# schemetic_phongbep.net
KiCad netlist of a schematic drawn in Altium Designer
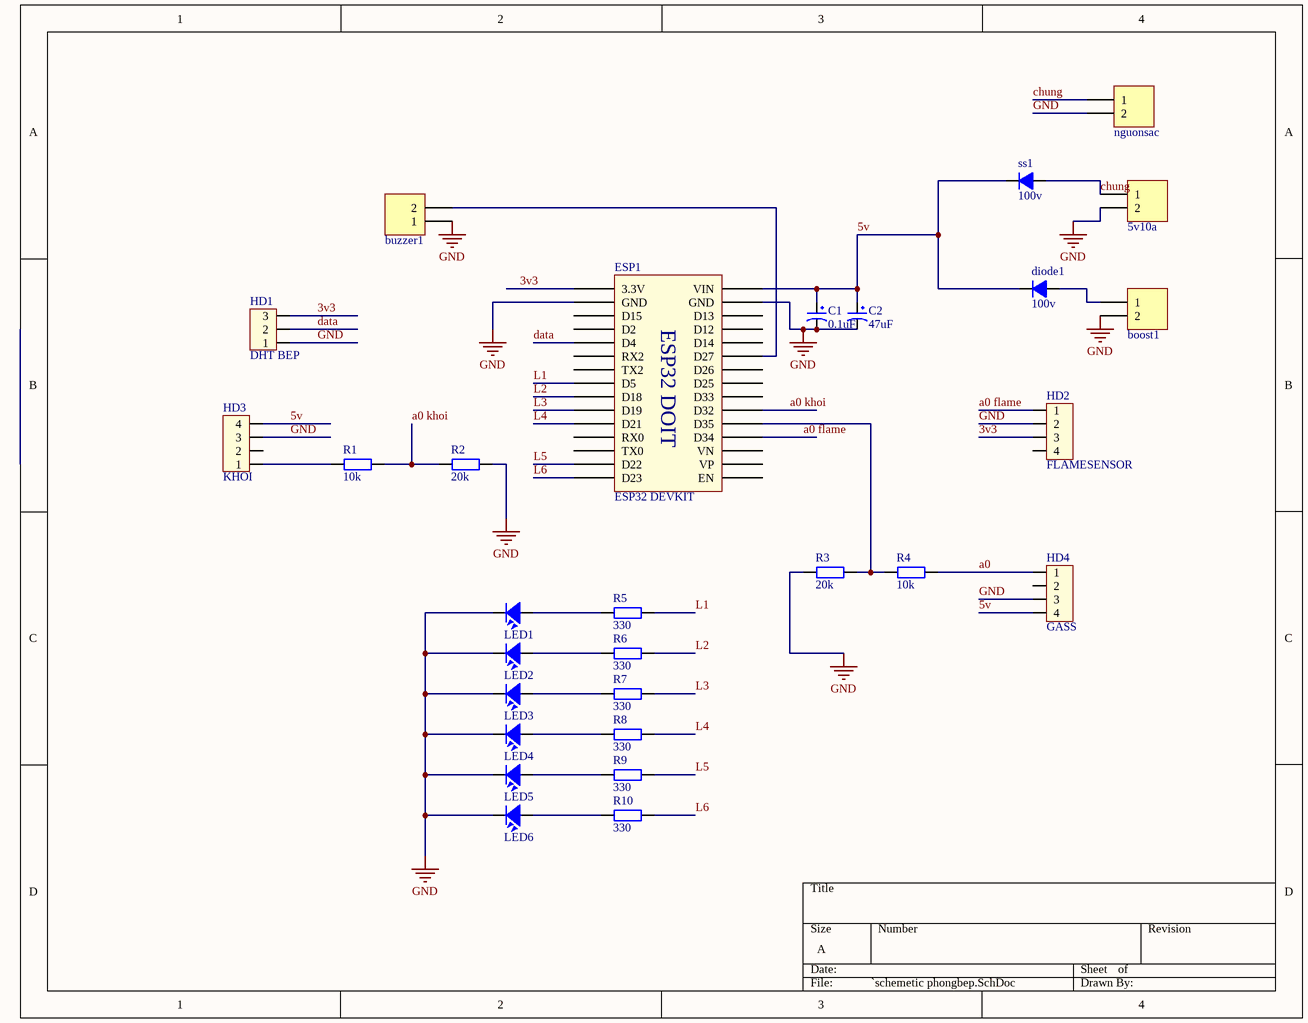
[diagram p0: `schemetic phongbep.SchDoc]

(export (version "E")
  (design (tool "Eeschema 10.0.6"))
  (components
    (comp (ref "5v10a")
      (value "Header 2_1")
      (footprint "HED2")
      (description "Header, 2-Pin")
      (fields (field (name "MANUFACTURER") "Generic Components"))
      (libsource (lib "") (part "Header 2_1_1"))
    )
    (comp (ref "boost1")
      (value "Header 2_1")
      (footprint "HED2")
      (description "Header, 2-Pin")
      (fields (field (name "MANUFACTURER") "Generic Components"))
      (libsource (lib "") (part "Header 2_1_1"))
    )
    (comp (ref "buzzer1")
      (value "Header 2_1")
      (footprint "HED2")
      (description "Header, 2-Pin")
      (fields (field (name "MANUFACTURER") "Generic Components"))
      (libsource (lib "syhaunguyen") (part "Header 2_1"))
    )
    (comp (ref "C1")
      (value "0.1uF")
      (footprint "tu hoa 5mm")
      (description "Cắm")
      (libsource (lib "Altium_Lib_by_KhueNguyenCreator") (part "Tu Hoa 0.1uF 50V 5x11"))
    )
    (comp (ref "C2")
      (value "47uF")
      (footprint "tu hoa 5mm")
      (description "Cắm")
      (libsource (lib "Altium_Lib_by_KhueNguyenCreator") (part "Tu Hoa 47uF 16V 5x10"))
    )
    (comp (ref "diode1")
      (value "100v")
      (footprint "DIODE 0.5A")
      (description "Cắm")
      (libsource (lib "Altium_Lib_by_KhueNguyenCreator") (part "Diode 1N4148"))
    )
    (comp (ref "ESP1")
      (value "ESP32 DEVKIT")
      (footprint "ESP32 WROOM 32 KIT")
      (libsource (lib "Altium_Lib_by_KhueNguyenCreator") (part "ESP32 WROOM 32 KIT"))
    )
    (comp (ref "HD1")
      (value "DHT BEP")
      (footprint "HED3")
      (description "Header 3 (Green)")
      (libsource (lib "syhaunguyen") (part "Hed3"))
    )
    (comp (ref "HD2")
      (value "FLAMESENSOR")
      (footprint "HED4")
      (description "Header 4 (Green)")
      (libsource (lib "syhaunguyen") (part "Hed4"))
    )
    (comp (ref "HD3")
      (value "KHOI")
      (footprint "HED4")
      (description "Header 4 (Green)")
      (libsource (lib "") (part "Hed4_1"))
    )
    (comp (ref "HD4")
      (value "GASS")
      (footprint "HED4")
      (description "Header 4 (Green)")
      (libsource (lib "syhaunguyen") (part "Hed4"))
    )
    (comp (ref "LED1")
      (value "LED")
      (footprint "LED-5-Green")
      (description "LED Single colour Green and Red")
      (libsource (lib "syhaunguyen") (part "LED"))
    )
    (comp (ref "LED2")
      (value "LED")
      (footprint "LED-5-Green")
      (description "LED Single colour Green and Red")
      (libsource (lib "syhaunguyen") (part "LED"))
    )
    (comp (ref "LED3")
      (value "LED")
      (footprint "LED-5-Green")
      (description "LED Single colour Green and Red")
      (libsource (lib "syhaunguyen") (part "LED"))
    )
    (comp (ref "LED4")
      (value "LED")
      (footprint "LED-5-Green")
      (description "LED Single colour Green and Red")
      (libsource (lib "syhaunguyen") (part "LED"))
    )
    (comp (ref "LED5")
      (value "LED")
      (footprint "LED-5-Green")
      (description "LED Single colour Green and Red")
      (libsource (lib "syhaunguyen") (part "LED"))
    )
    (comp (ref "LED6")
      (value "LED")
      (footprint "LED-5-Green")
      (description "LED Single colour Green and Red")
      (libsource (lib "syhaunguyen") (part "LED"))
    )
    (comp (ref "nguonsac")
      (value "Header 2_1")
      (footprint "HED2")
      (description "Header, 2-Pin")
      (fields (field (name "MANUFACTURER") "Generic Components"))
      (libsource (lib "") (part "Header 2_1_1"))
    )
    (comp (ref "R1")
      (value "10k")
      (footprint "R1/4W")
      (description "Resistor 1/4W")
      (libsource (lib "syhaunguyen") (part "R1/4W"))
    )
    (comp (ref "R2")
      (value "20k")
      (footprint "R1/4W")
      (description "Resistor 1/4W")
      (libsource (lib "syhaunguyen") (part "R1/4W"))
    )
    (comp (ref "R3")
      (value "20k")
      (footprint "R1/4W")
      (description "Resistor 1/4W")
      (libsource (lib "syhaunguyen") (part "R1/4W"))
    )
    (comp (ref "R4")
      (value "10k")
      (footprint "R1/4W")
      (description "Resistor 1/4W")
      (libsource (lib "syhaunguyen") (part "R1/4W"))
    )
    (comp (ref "R5")
      (value "330")
      (footprint "R1/4W")
      (description "Resistor 1/4W")
      (libsource (lib "syhaunguyen") (part "R1/4W"))
    )
    (comp (ref "R6")
      (value "330")
      (footprint "R1/4W")
      (description "Resistor 1/4W")
      (libsource (lib "syhaunguyen") (part "R1/4W"))
    )
    (comp (ref "R7")
      (value "330")
      (footprint "R1/4W")
      (description "Resistor 1/4W")
      (libsource (lib "syhaunguyen") (part "R1/4W"))
    )
    (comp (ref "R8")
      (value "330")
      (footprint "R1/4W")
      (description "Resistor 1/4W")
      (libsource (lib "syhaunguyen") (part "R1/4W"))
    )
    (comp (ref "R9")
      (value "330")
      (footprint "R1/4W")
      (description "Resistor 1/4W")
      (libsource (lib "syhaunguyen") (part "R1/4W"))
    )
    (comp (ref "R10")
      (value "330")
      (footprint "R1/4W")
      (description "Resistor 1/4W")
      (libsource (lib "syhaunguyen") (part "R1/4W"))
    )
    (comp (ref "ss1")
      (value "100v")
      (footprint "DIODE 0.5A")
      (description "Cắm")
      (libsource (lib "Altium_Lib_by_KhueNguyenCreator") (part "Diode 1N4148"))
    )
  )
  (nets
    (net (code "1") (name "/3v3") (class "Default")
      (node (ref "ESP1") (pin "16") (pinfunction "3.3V_16") (pintype "passive"))
      (node (ref "HD1") (pin "3") (pinfunction "3_3") (pintype "passive"))
      (node (ref "HD2") (pin "3") (pinfunction "3_3") (pintype "passive"))
    )
    (net (code "2") (name "/5v") (class "Default")
      (node (ref "C1") (pin "1") (pinfunction "1_1") (pintype "passive"))
      (node (ref "C2") (pin "1") (pinfunction "1_1") (pintype "passive"))
      (node (ref "ESP1") (pin "15") (pinfunction "VIN_15") (pintype "passive"))
      (node (ref "HD3") (pin "4") (pinfunction "4_4") (pintype "passive"))
      (node (ref "HD4") (pin "4") (pinfunction "4_4") (pintype "passive"))
      (node (ref "diode1") (pin "2") (pinfunction "K_2") (pintype "passive"))
      (node (ref "ss1") (pin "2") (pinfunction "K_2") (pintype "passive"))
    )
    (net (code "3") (name "/L1") (class "Default")
      (node (ref "ESP1") (pin "23") (pinfunction "D5_23") (pintype "passive"))
      (node (ref "R5") (pin "2") (pinfunction "2_2") (pintype "passive"))
    )
    (net (code "4") (name "/L2") (class "Default")
      (node (ref "ESP1") (pin "24") (pinfunction "D18_24") (pintype "passive"))
      (node (ref "R6") (pin "2") (pinfunction "2_2") (pintype "passive"))
    )
    (net (code "5") (name "/L3") (class "Default")
      (node (ref "ESP1") (pin "25") (pinfunction "D19_25") (pintype "passive"))
      (node (ref "R7") (pin "2") (pinfunction "2_2") (pintype "passive"))
    )
    (net (code "6") (name "/L4") (class "Default")
      (node (ref "ESP1") (pin "26") (pinfunction "D21_26") (pintype "passive"))
      (node (ref "R8") (pin "2") (pinfunction "2_2") (pintype "passive"))
    )
    (net (code "7") (name "/L5") (class "Default")
      (node (ref "ESP1") (pin "29") (pinfunction "D22_29") (pintype "passive"))
      (node (ref "R9") (pin "2") (pinfunction "2_2") (pintype "passive"))
    )
    (net (code "8") (name "/L6") (class "Default")
      (node (ref "ESP1") (pin "30") (pinfunction "D23_30") (pintype "passive"))
      (node (ref "R10") (pin "2") (pinfunction "2_2") (pintype "passive"))
    )
    (net (code "9") (name "/a0") (class "Default")
      (node (ref "HD4") (pin "1") (pinfunction "1_1") (pintype "passive"))
      (node (ref "R4") (pin "2") (pinfunction "2_2") (pintype "passive"))
    )
    (net (code "10") (name "/a0 flame") (class "Default")
      (node (ref "ESP1") (pin "4") (pinfunction "D34_4") (pintype "passive"))
      (node (ref "HD2") (pin "1") (pinfunction "1_1") (pintype "passive"))
    )
    (net (code "11") (name "/a0 khoi") (class "Default")
      (node (ref "ESP1") (pin "6") (pinfunction "D32_6") (pintype "passive"))
      (node (ref "R1") (pin "2") (pinfunction "2_2") (pintype "passive"))
      (node (ref "R2") (pin "2") (pinfunction "2_2") (pintype "passive"))
    )
    (net (code "12") (name "/chung") (class "Default")
      (node (ref "5v10a") (pin "1") (pinfunction "1_1") (pintype "passive"))
      (node (ref "nguonsac") (pin "1") (pinfunction "1_1") (pintype "passive"))
      (node (ref "ss1") (pin "1") (pinfunction "A_1") (pintype "passive"))
    )
    (net (code "13") (name "/data") (class "Default")
      (node (ref "ESP1") (pin "20") (pinfunction "D4_20") (pintype "passive"))
      (node (ref "HD1") (pin "2") (pinfunction "2_2") (pintype "passive"))
    )
    (net (code "14") (name "GND") (class "Default")
      (node (ref "5v10a") (pin "2") (pinfunction "2_2") (pintype "passive"))
      (node (ref "C1") (pin "2") (pinfunction "2_2") (pintype "passive"))
      (node (ref "C2") (pin "2") (pinfunction "2_2") (pintype "passive"))
      (node (ref "ESP1") (pin "14") (pinfunction "GND_14") (pintype "passive"))
      (node (ref "ESP1") (pin "17") (pinfunction "GND_17") (pintype "passive"))
      (node (ref "HD1") (pin "1") (pinfunction "1_1") (pintype "passive"))
      (node (ref "HD2") (pin "2") (pinfunction "2_2") (pintype "passive"))
      (node (ref "HD3") (pin "3") (pinfunction "3_3") (pintype "passive"))
      (node (ref "HD4") (pin "3") (pinfunction "3_3") (pintype "passive"))
      (node (ref "LED1") (pin "2") (pinfunction "2_2") (pintype "passive"))
      (node (ref "LED2") (pin "2") (pinfunction "2_2") (pintype "passive"))
      (node (ref "LED3") (pin "2") (pinfunction "2_2") (pintype "passive"))
      (node (ref "LED4") (pin "2") (pinfunction "2_2") (pintype "passive"))
      (node (ref "LED5") (pin "2") (pinfunction "2_2") (pintype "passive"))
      (node (ref "LED6") (pin "2") (pinfunction "2_2") (pintype "passive"))
      (node (ref "R2") (pin "1") (pinfunction "1_1") (pintype "passive"))
      (node (ref "R3") (pin "2") (pinfunction "2_2") (pintype "passive"))
      (node (ref "boost1") (pin "2") (pinfunction "2_2") (pintype "passive"))
      (node (ref "buzzer1") (pin "1") (pinfunction "1_1") (pintype "passive"))
      (node (ref "nguonsac") (pin "2") (pinfunction "2_2") (pintype "passive"))
    )
    (net (code "15") (name "Net-(ESP1-D27)") (class "Default")
      (node (ref "ESP1") (pin "10") (pinfunction "D27_10") (pintype "passive"))
      (node (ref "buzzer1") (pin "2") (pinfunction "2_2") (pintype "passive"))
    )
    (net (code "16") (name "Net-(ESP1-D35)") (class "Default")
      (node (ref "ESP1") (pin "5") (pinfunction "D35_5") (pintype "passive"))
      (node (ref "R3") (pin "1") (pinfunction "1_1") (pintype "passive"))
      (node (ref "R4") (pin "1") (pinfunction "1_1") (pintype "passive"))
    )
    (net (code "17") (name "Net-(HD3-Pad1)") (class "Default")
      (node (ref "HD3") (pin "1") (pinfunction "1_1") (pintype "passive"))
      (node (ref "R1") (pin "1") (pinfunction "1_1") (pintype "passive"))
    )
    (net (code "18") (name "Net-(LED1-Pad1)") (class "Default")
      (node (ref "LED1") (pin "1") (pinfunction "1_1") (pintype "passive"))
      (node (ref "R5") (pin "1") (pinfunction "1_1") (pintype "passive"))
    )
    (net (code "19") (name "Net-(LED2-Pad1)") (class "Default")
      (node (ref "LED2") (pin "1") (pinfunction "1_1") (pintype "passive"))
      (node (ref "R6") (pin "1") (pinfunction "1_1") (pintype "passive"))
    )
    (net (code "20") (name "Net-(LED3-Pad1)") (class "Default")
      (node (ref "LED3") (pin "1") (pinfunction "1_1") (pintype "passive"))
      (node (ref "R7") (pin "1") (pinfunction "1_1") (pintype "passive"))
    )
    (net (code "21") (name "Net-(LED4-Pad1)") (class "Default")
      (node (ref "LED4") (pin "1") (pinfunction "1_1") (pintype "passive"))
      (node (ref "R8") (pin "1") (pinfunction "1_1") (pintype "passive"))
    )
    (net (code "22") (name "Net-(LED5-Pad1)") (class "Default")
      (node (ref "LED5") (pin "1") (pinfunction "1_1") (pintype "passive"))
      (node (ref "R9") (pin "1") (pinfunction "1_1") (pintype "passive"))
    )
    (net (code "23") (name "Net-(LED6-Pad1)") (class "Default")
      (node (ref "LED6") (pin "1") (pinfunction "1_1") (pintype "passive"))
      (node (ref "R10") (pin "1") (pinfunction "1_1") (pintype "passive"))
    )
    (net (code "24") (name "Net-(diode1-A)") (class "Default")
      (node (ref "boost1") (pin "1") (pinfunction "1_1") (pintype "passive"))
      (node (ref "diode1") (pin "1") (pinfunction "A_1") (pintype "passive"))
    )
    (net (code "25") (name "unconnected-(ESP1-D2-Pad19)") (class "Default")
      (node (ref "ESP1") (pin "19") (pinfunction "D2_19") (pintype "passive"))
    )
    (net (code "26") (name "unconnected-(ESP1-D12-Pad12)") (class "Default")
      (node (ref "ESP1") (pin "12") (pinfunction "D12_12") (pintype "passive"))
    )
    (net (code "27") (name "unconnected-(ESP1-D13-Pad13)") (class "Default")
      (node (ref "ESP1") (pin "13") (pinfunction "D13_13") (pintype "passive"))
    )
    (net (code "28") (name "unconnected-(ESP1-D14-Pad11)") (class "Default")
      (node (ref "ESP1") (pin "11") (pinfunction "D14_11") (pintype "passive"))
    )
    (net (code "29") (name "unconnected-(ESP1-D15-Pad18)") (class "Default")
      (node (ref "ESP1") (pin "18") (pinfunction "D15_18") (pintype "passive"))
    )
    (net (code "30") (name "unconnected-(ESP1-D25-Pad8)") (class "Default")
      (node (ref "ESP1") (pin "8") (pinfunction "D25_8") (pintype "passive"))
    )
    (net (code "31") (name "unconnected-(ESP1-D26-Pad9)") (class "Default")
      (node (ref "ESP1") (pin "9") (pinfunction "D26_9") (pintype "passive"))
    )
    (net (code "32") (name "unconnected-(ESP1-D33-Pad7)") (class "Default")
      (node (ref "ESP1") (pin "7") (pinfunction "D33_7") (pintype "passive"))
    )
    (net (code "33") (name "unconnected-(ESP1-EN-Pad1)") (class "Default")
      (node (ref "ESP1") (pin "1") (pinfunction "EN_1") (pintype "passive"))
    )
    (net (code "34") (name "unconnected-(ESP1-RX0-Pad27)") (class "Default")
      (node (ref "ESP1") (pin "27") (pinfunction "RX0_27") (pintype "passive"))
    )
    (net (code "35") (name "unconnected-(ESP1-RX2-Pad21)") (class "Default")
      (node (ref "ESP1") (pin "21") (pinfunction "RX2_21") (pintype "passive"))
    )
    (net (code "36") (name "unconnected-(ESP1-TX0-Pad28)") (class "Default")
      (node (ref "ESP1") (pin "28") (pinfunction "TX0_28") (pintype "passive"))
    )
    (net (code "37") (name "unconnected-(ESP1-TX2-Pad22)") (class "Default")
      (node (ref "ESP1") (pin "22") (pinfunction "TX2_22") (pintype "passive"))
    )
    (net (code "38") (name "unconnected-(ESP1-VN-Pad3)") (class "Default")
      (node (ref "ESP1") (pin "3") (pinfunction "VN_3") (pintype "passive"))
    )
    (net (code "39") (name "unconnected-(ESP1-VP-Pad2)") (class "Default")
      (node (ref "ESP1") (pin "2") (pinfunction "VP_2") (pintype "passive"))
    )
    (net (code "40") (name "unconnected-(HD2-Pad4)") (class "Default")
      (node (ref "HD2") (pin "4") (pinfunction "4_4") (pintype "passive"))
    )
    (net (code "41") (name "unconnected-(HD3-Pad2)") (class "Default")
      (node (ref "HD3") (pin "2") (pinfunction "2_2") (pintype "passive"))
    )
    (net (code "42") (name "unconnected-(HD4-Pad2)") (class "Default")
      (node (ref "HD4") (pin "2") (pinfunction "2_2") (pintype "passive"))
    )
  )
)
